# ACT01_RS232_V3_0.net
KiCad netlist of a schematic drawn in Altium Designer
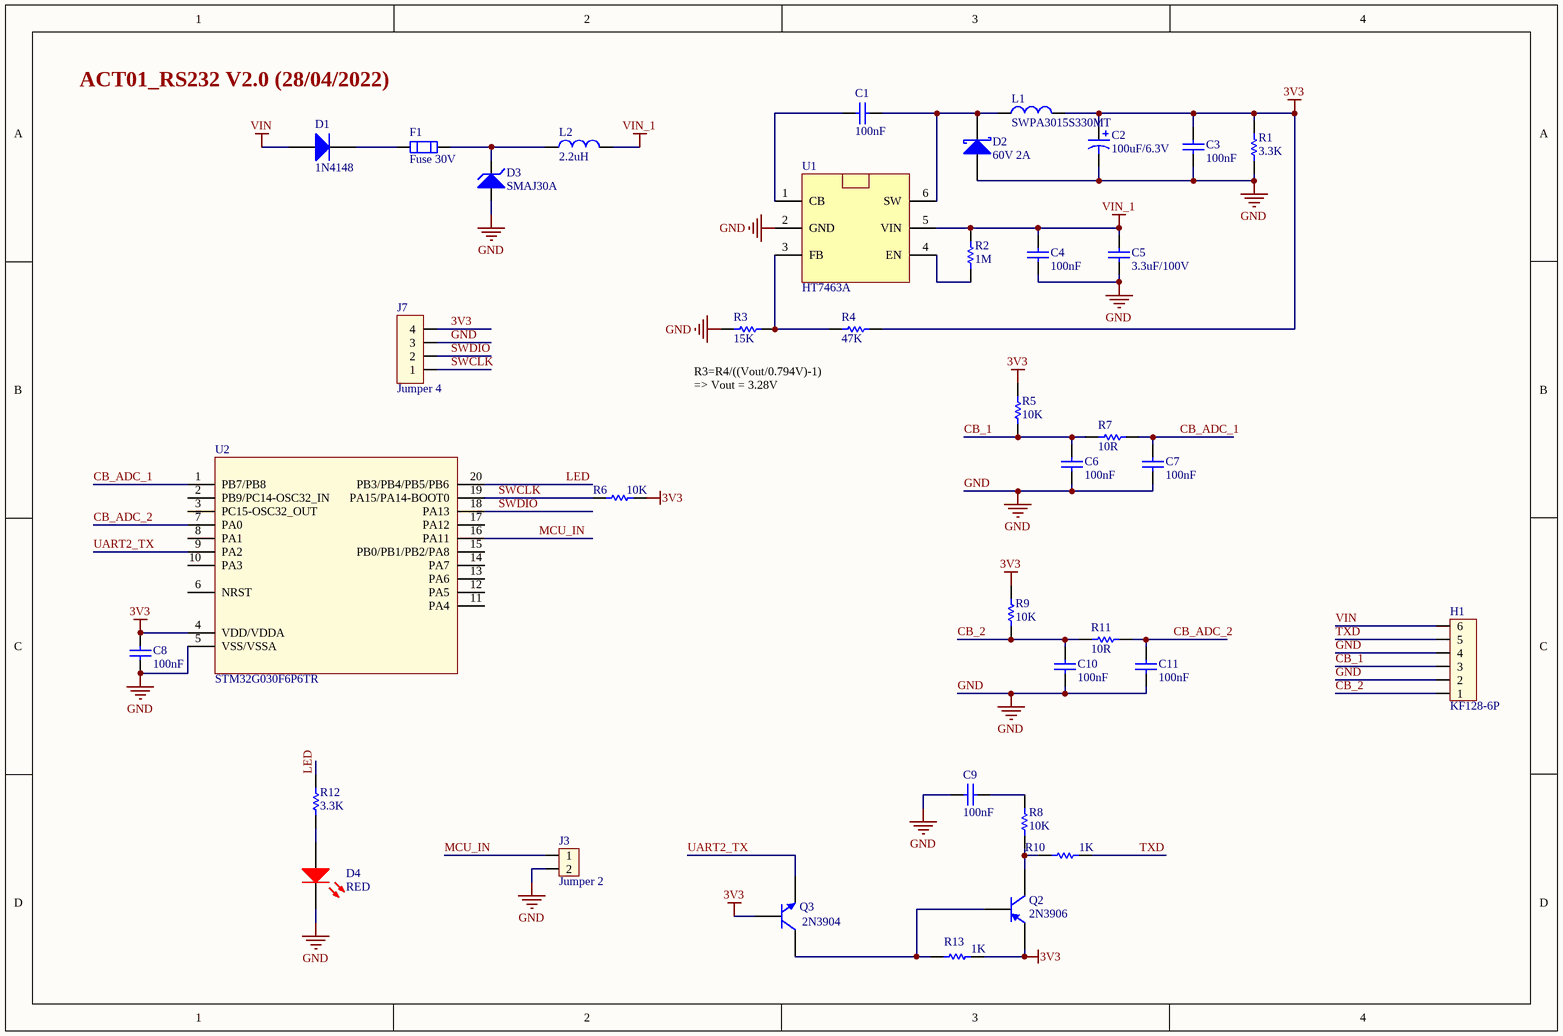
[diagram p0: ACT01_RS232 V3.0.SchDoc]

(export (version "E")
  (design (tool "Eeschema 10.0.6"))
  (components
    (comp (ref "C1")
      (value "100nF")
      (footprint "0603 - C")
      (description "CAP CER 100nF 50V C0G/NP0 0603")
      (fields (field (name "MPN") "CL10C104JB8NNNC") (field (name "MFR") "SAMSUNG"))
      (libsource (lib "Library_Chip1") (part "Cap 0603 100nF"))
    )
    (comp (ref "C2")
      (value "100uF/6.3V")
      (footprint "3528 - TANTALUM")
      (description "CAP TANT 100UF 6.3V 10% 1411")
      (fields (field (name "MPN") "T491B107K006AT") (field (name "MFR") "Kemet"))
      (libsource (lib "Library_Chip1") (part "Cap Tan 3528 100uF/6.3V"))
    )
    (comp (ref "C3")
      (value "100nF")
      (footprint "0603 - C")
      (description "CAP CER 100nF 50V C0G/NP0 0603")
      (fields (field (name "MPN") "CL10C104JB8NNNC") (field (name "MFR") "SAMSUNG"))
      (libsource (lib "Library_Chip1") (part "Cap 0603 100nF"))
    )
    (comp (ref "C4")
      (value "100nF")
      (footprint "0603 - C")
      (description "CAP CER 100nF 50V C0G/NP0 0603")
      (fields (field (name "MPN") "CL10C104JB8NNNC") (field (name "MFR") "SAMSUNG"))
      (libsource (lib "Library_Chip1") (part "Cap 0603 100nF"))
    )
    (comp (ref "C5")
      (value "3.3uF/100V")
      (footprint "1210 - C")
      (description "CAP CER 3.3UF 100V X7S 1210")
      (fields (field (name "MPN") "C3225X7S2A335M200AB") (field (name "MFR") "TDK Corporation"))
      (libsource (lib "Library_Chip1") (part "Cap 1210 3.3uF"))
    )
    (comp (ref "C6")
      (value "100nF")
      (footprint "0603 - C")
      (description "CAP CER 100nF 50V C0G/NP0 0603")
      (fields (field (name "MPN") "CL10C104JB8NNNC") (field (name "MFR") "SAMSUNG"))
      (libsource (lib "Library_Chip1") (part "Cap 0603 100nF"))
    )
    (comp (ref "C7")
      (value "100nF")
      (footprint "0603 - C")
      (description "CAP CER 100nF 50V C0G/NP0 0603")
      (fields (field (name "MPN") "CL10C104JB8NNNC") (field (name "MFR") "SAMSUNG"))
      (libsource (lib "Library_Chip1") (part "Cap 0603 100nF"))
    )
    (comp (ref "C8")
      (value "100nF")
      (footprint "0603 - C")
      (description "CAP CER 100nF 50V C0G/NP0 0603")
      (fields (field (name "MPN") "CL10C104JB8NNNC") (field (name "MFR") "SAMSUNG"))
      (libsource (lib "Library_Chip") (part "Cap 0603 100nF"))
    )
    (comp (ref "C9")
      (value "100nF")
      (footprint "0603 - C")
      (description "CAP CER 100nF 50V C0G/NP0 0603")
      (fields (field (name "MPN") "CL10C104JB8NNNC") (field (name "MFR") "SAMSUNG"))
      (libsource (lib "Library_Chip") (part "Cap 0603 100nF"))
    )
    (comp (ref "C10")
      (value "100nF")
      (footprint "0603 - C")
      (description "CAP CER 100nF 50V C0G/NP0 0603")
      (fields (field (name "MPN") "CL10C104JB8NNNC") (field (name "MFR") "SAMSUNG"))
      (libsource (lib "Library_Chip1") (part "Cap 0603 100nF"))
    )
    (comp (ref "C11")
      (value "100nF")
      (footprint "0603 - C")
      (description "CAP CER 100nF 50V C0G/NP0 0603")
      (fields (field (name "MPN") "CL10C104JB8NNNC") (field (name "MFR") "SAMSUNG"))
      (libsource (lib "Library_Chip1") (part "Cap 0603 100nF"))
    )
    (comp (ref "D1")
      (value "1N4148")
      (footprint "SOD-123")
      (description "DIODE GEN PURP 100V 300MA SOD123")
      (fields (field (name "MPN") "1N4148W-7-F") (field (name "MFR") "DIODES"))
      (libsource (lib "Library_Chip") (part "Diode 1N4148"))
    )
    (comp (ref "D2")
      (value "60V 2A")
      (footprint "SOD-123")
      (description "DIODE SCHOTTKY 60V 2A SOD123W")
      (fields (field (name "MPN") "PMEG6020ER,115") (field (name "MFR") "NXP"))
      (libsource (lib "Library_Chip") (part "Diode PMEG6020ER"))
    )
    (comp (ref "D3")
      (value "SMAJ30A")
      (footprint "Diode - SMA")
      (description "TVS DIODE 30V 48.4V DO214AC")
      (fields (field (name "MFR") "Littelfuse Inc."))
      (libsource (lib "Library_Chip") (part "Diode SMAJ30A"))
    )
    (comp (ref "D4")
      (value "RED")
      (footprint "LED - 0603 - R")
      (description "LED RED CLEAR 0603 SMD")
      (fields (field (name "MFR") "Everlight") (field (name "MPN") "QTLP601CRTR"))
      (libsource (lib "Library_Chip") (part "LED 0603 RED"))
    )
    (comp (ref "F1")
      (value "Fuse 30V")
      (footprint "1206 - Fuse")
      (description "PTC RESET FUSE 30V 0.125A 1206")
      (fields (field (name "MFR") "BrightKing") (field (name "MPN") "SMD1206B012TF"))
      (libsource (lib "Library_Chip") (part "Fuse 30V - 0.125A"))
    )
    (comp (ref "H1")
      (value "KF128-6P")
      (footprint "KF128 - 6P")
      (description "6-Pin Plug-in Terminal Block Connector 5.08mm Pitch Through Hole")
      (fields (field (name "MPN") "KF128 - 6P") (field (name "MFR") "China"))
      (libsource (lib "Library_ Connector") (part "HD KF128 6P"))
    )
    (comp (ref "J3")
      (value "Jumper 2")
      (footprint "JP2")
      (description "Jumper 2, 2.54mmx2")
      (libsource (lib "Library_ Connector") (part "JP2"))
    )
    (comp (ref "J7")
      (value "Jumper 4")
      (footprint "JP4 2mm")
      (description "Jumper 4, 2.54mmx4")
      (libsource (lib "Library_ Connector") (part "JP4"))
    )
    (comp (ref "L1")
      (value "SWPA3015S330MT")
      (footprint "IND_3x3")
      (description "FIXED IND 33UH 430MA 1.066OHM SM")
      (fields (field (name "MFR") "Shenzhen Sunlord Electronics Co., Ltd."))
      (libsource (lib "Library_Chip") (part "Inductor 33uH"))
    )
    (comp (ref "L2")
      (value "2.2uH")
      (footprint "1210 - L")
      (description "FIXED IND 2.2UH 1.6A 76 MOHM SMD")
      (fields (field (name "MPN") "LQH32PN2R2NN0") (field (name "MFR") "Murata"))
      (libsource (lib "Library_Chip") (part "Inductor 3225 2.2uH"))
    )
    (comp (ref "Q2")
      (value "2N3906")
      (footprint "SOT23B")
      (description "TRANS PNP 40V 0.2A SOT23")
      (fields (field (name "MPN") "MMBT3906") (field (name "MFR") "Fairchild"))
      (libsource (lib "Library_Chip") (part "Transistor 2N3906"))
    )
    (comp (ref "Q3")
      (value "2N3904")
      (footprint "SOT23B")
      (description "TRANS NPN 40V 0.2A SOT-23")
      (fields (field (name "MPN") "MMBT3904") (field (name "MFR") "Fairchild"))
      (libsource (lib "Library_Chip") (part "Transistor 2N3904"))
    )
    (comp (ref "R1")
      (value "3.3K")
      (footprint "0603 - R")
      (description "RES SMD 3.3K OHM 1% 1/10W 0603")
      (fields (field (name "MFR") "Yageo") (field (name "MPN") "RC0603FR-073K3L"))
      (libsource (lib "Library_Chip") (part "Res 0603 3.3K"))
    )
    (comp (ref "R2")
      (value "1M")
      (footprint "0603 - R")
      (description "RES SMD 1M OHM 1% 1/10W 0603")
      (fields (field (name "MFR") "Yageo") (field (name "MPN") "RC0603FR-071ML"))
      (libsource (lib "Library_Chip1") (part "Res 0603 1M"))
    )
    (comp (ref "R3")
      (value "15K")
      (footprint "0603 - R")
      (description "RES SMD 15K OHM 1% 1/10W 0603")
      (fields (field (name "MFR") "Yageo") (field (name "MPN") "RC0603FR-0715KL"))
      (libsource (lib "Library_Chip1") (part "Res 0603 15K"))
    )
    (comp (ref "R4")
      (value "47K")
      (footprint "0603 - R")
      (description "RES SMD 47K OHM 1% 1/10W 0603")
      (fields (field (name "MFR") "Yageo") (field (name "MPN") "RE0603FRE0747KL"))
      (libsource (lib "Library_Chip1") (part "Res 0603 47K"))
    )
    (comp (ref "R5")
      (value "10K")
      (footprint "0603 - R")
      (description "RES SMD 10K OHM 1% 1/10W 0603")
      (fields (field (name "MFR") "Yageo") (field (name "MPN") "RC0603FR-0710KL"))
      (libsource (lib "Library_Chip") (part "Res 0603 10K"))
    )
    (comp (ref "R6")
      (value "10K")
      (footprint "0603 - R")
      (description "RES SMD 10K OHM 1% 1/10W 0603")
      (fields (field (name "MFR") "Yageo") (field (name "MPN") "RC0603FR-0710KL"))
      (libsource (lib "Library_Chip") (part "Res 0603 10K"))
    )
    (comp (ref "R7")
      (value "10R")
      (footprint "0603 - R")
      (description "RES SMD 10 OHM 1% 1/10W 0603")
      (fields (field (name "MFR") "Yageo") (field (name "MPN") "RC0603FR-0710RL"))
      (libsource (lib "Library_Chip") (part "Res 0603 10R"))
    )
    (comp (ref "R8")
      (value "10K")
      (footprint "0603 - R")
      (description "RES SMD 10K OHM 1% 1/10W 0603")
      (fields (field (name "MFR") "Yageo") (field (name "MPN") "RC0603FR-0710KL"))
      (libsource (lib "Library_Chip") (part "Res 0603 10K"))
    )
    (comp (ref "R9")
      (value "10K")
      (footprint "0603 - R")
      (description "RES SMD 10K OHM 1% 1/10W 0603")
      (fields (field (name "MFR") "Yageo") (field (name "MPN") "RC0603FR-0710KL"))
      (libsource (lib "Library_Chip") (part "Res 0603 10K"))
    )
    (comp (ref "R10")
      (value "1K")
      (footprint "0603 - R")
      (description "RES SMD 1K OHM 1% 1/10W 0603")
      (fields (field (name "MFR") "Yageo") (field (name "MPN") "RC0603FR-071KL"))
      (libsource (lib "Library_Chip") (part "Res 0603 1K"))
    )
    (comp (ref "R11")
      (value "10R")
      (footprint "0603 - R")
      (description "RES SMD 10 OHM 1% 1/10W 0603")
      (fields (field (name "MFR") "Yageo") (field (name "MPN") "RC0603FR-0710RL"))
      (libsource (lib "Library_Chip") (part "Res 0603 10R"))
    )
    (comp (ref "R12")
      (value "3.3K")
      (footprint "0603 - R")
      (description "RES SMD 3.3K OHM 1% 1/10W 0603")
      (fields (field (name "MFR") "Yageo") (field (name "MPN") "RC0603FR-073K3L"))
      (libsource (lib "Library_Chip") (part "Res 0603 3.3K"))
    )
    (comp (ref "R13")
      (value "1K")
      (footprint "0603 - R")
      (description "RES SMD 1K OHM 1% 1/10W 0603")
      (fields (field (name "MFR") "Yageo") (field (name "MPN") "RC0603FR-071KL"))
      (libsource (lib "Library_Chip") (part "Res 0603 1K"))
    )
    (comp (ref "U1")
      (value "HT7463A")
      (footprint "SOT23-6_L")
      (description "52V/600mA, 1.25MHz/550kHz\r\nAsynchronous Step Down Converter")
      (fields (field (name "MFR") "Holtek"))
      (libsource (lib "Library_IC") (part "HT7463A/HT7463B"))
    )
    (comp (ref "U2")
      (value "STM32G030F6P6TR")
      (footprint "TSSOP20")
      (description "IC MCU 32BIT 32KB FLASH 20TSSOP")
      (fields (field (name "MPN") "STMicroelectronics"))
      (libsource (lib "Library_IC") (part "STM32G030F6P6TR"))
    )
  )
  (nets
    (net (code "1") (name "/CB_1") (class "Default")
      (node (ref "C6") (pin "2") (pinfunction "2_2") (pintype "passive"))
      (node (ref "H1") (pin "3") (pinfunction "3_3") (pintype "passive"))
      (node (ref "R5") (pin "1") (pinfunction "1_1") (pintype "passive"))
      (node (ref "R7") (pin "1") (pinfunction "1_1") (pintype "passive"))
    )
    (net (code "2") (name "/CB_2") (class "Default")
      (node (ref "C10") (pin "2") (pinfunction "2_2") (pintype "passive"))
      (node (ref "H1") (pin "1") (pinfunction "1_1") (pintype "passive"))
      (node (ref "R11") (pin "1") (pinfunction "1_1") (pintype "passive"))
      (node (ref "R9") (pin "1") (pinfunction "1_1") (pintype "passive"))
    )
    (net (code "3") (name "/CB_ADC_1") (class "Default")
      (node (ref "C7") (pin "2") (pinfunction "2_2") (pintype "passive"))
      (node (ref "R7") (pin "2") (pinfunction "2_2") (pintype "passive"))
      (node (ref "U2") (pin "1") (pinfunction "PB7/PB8_1") (pintype "power_in"))
    )
    (net (code "4") (name "/CB_ADC_2") (class "Default")
      (node (ref "C11") (pin "2") (pinfunction "2_2") (pintype "passive"))
      (node (ref "R11") (pin "2") (pinfunction "2_2") (pintype "passive"))
      (node (ref "U2") (pin "7") (pinfunction "PA0_7") (pintype "power_in"))
    )
    (net (code "5") (name "/LED") (class "Default")
      (node (ref "R12") (pin "2") (pinfunction "2_2") (pintype "passive"))
      (node (ref "U2") (pin "20") (pinfunction "PB3/PB4/PB5/PB6_20") (pintype "power_in"))
    )
    (net (code "6") (name "/MCU_IN") (class "Default")
      (node (ref "J3") (pin "1") (pinfunction "1_1") (pintype "passive"))
      (node (ref "U2") (pin "16") (pinfunction "PA11_16") (pintype "power_in"))
    )
    (net (code "7") (name "/SWCLK") (class "Default")
      (node (ref "J7") (pin "1") (pinfunction "1_1") (pintype "passive"))
      (node (ref "R6") (pin "1") (pinfunction "1_1") (pintype "passive"))
      (node (ref "U2") (pin "19") (pinfunction "PA15/PA14-BOOT0_19") (pintype "power_in"))
    )
    (net (code "8") (name "/SWDIO") (class "Default")
      (node (ref "J7") (pin "2") (pinfunction "2_2") (pintype "passive"))
      (node (ref "U2") (pin "18") (pinfunction "PA13_18") (pintype "power_in"))
    )
    (net (code "9") (name "/TXD") (class "Default")
      (node (ref "H1") (pin "5") (pinfunction "5_5") (pintype "passive"))
      (node (ref "R10") (pin "2") (pinfunction "2_2") (pintype "passive"))
    )
    (net (code "10") (name "/UART2_TX") (class "Default")
      (node (ref "Q3") (pin "2") (pinfunction "E_2") (pintype "passive"))
      (node (ref "U2") (pin "9") (pinfunction "PA2_9") (pintype "power_in"))
    )
    (net (code "11") (name "3V3") (class "Default")
      (node (ref "C2") (pin "1") (pinfunction "1_1") (pintype "passive"))
      (node (ref "C3") (pin "2") (pinfunction "2_2") (pintype "passive"))
      (node (ref "C8") (pin "2") (pinfunction "2_2") (pintype "passive"))
      (node (ref "J7") (pin "4") (pinfunction "4_4") (pintype "passive"))
      (node (ref "L1") (pin "2") (pinfunction "2_2") (pintype "passive"))
      (node (ref "Q2") (pin "2") (pinfunction "E_2") (pintype "passive"))
      (node (ref "Q3") (pin "1") (pinfunction "B_1") (pintype "passive"))
      (node (ref "R1") (pin "2") (pinfunction "2_2") (pintype "passive"))
      (node (ref "R13") (pin "2") (pinfunction "2_2") (pintype "passive"))
      (node (ref "R4") (pin "2") (pinfunction "2_2") (pintype "passive"))
      (node (ref "R5") (pin "2") (pinfunction "2_2") (pintype "passive"))
      (node (ref "R6") (pin "2") (pinfunction "2_2") (pintype "passive"))
      (node (ref "R9") (pin "2") (pinfunction "2_2") (pintype "passive"))
      (node (ref "U2") (pin "4") (pinfunction "VDD/VDDA_4") (pintype "power_in"))
    )
    (net (code "12") (name "GND") (class "Default")
      (node (ref "C10") (pin "1") (pinfunction "1_1") (pintype "passive"))
      (node (ref "C11") (pin "1") (pinfunction "1_1") (pintype "passive"))
      (node (ref "C2") (pin "2") (pinfunction "2_2") (pintype "passive"))
      (node (ref "C3") (pin "1") (pinfunction "1_1") (pintype "passive"))
      (node (ref "C4") (pin "1") (pinfunction "1_1") (pintype "passive"))
      (node (ref "C5") (pin "1") (pinfunction "1_1") (pintype "passive"))
      (node (ref "C6") (pin "1") (pinfunction "1_1") (pintype "passive"))
      (node (ref "C7") (pin "1") (pinfunction "1_1") (pintype "passive"))
      (node (ref "C8") (pin "1") (pinfunction "1_1") (pintype "passive"))
      (node (ref "C9") (pin "1") (pinfunction "1_1") (pintype "passive"))
      (node (ref "D2") (pin "1") (pinfunction "A_1") (pintype "passive"))
      (node (ref "D3") (pin "1") (pinfunction "A_1") (pintype "passive"))
      (node (ref "D4") (pin "2") (pinfunction "K_2") (pintype "passive"))
      (node (ref "H1") (pin "2") (pinfunction "2_2") (pintype "passive"))
      (node (ref "H1") (pin "4") (pinfunction "4_4") (pintype "passive"))
      (node (ref "J3") (pin "2") (pinfunction "2_2") (pintype "passive"))
      (node (ref "J7") (pin "3") (pinfunction "3_3") (pintype "passive"))
      (node (ref "R1") (pin "1") (pinfunction "1_1") (pintype "passive"))
      (node (ref "R3") (pin "2") (pinfunction "2_2") (pintype "passive"))
      (node (ref "U1") (pin "2") (pinfunction "GND_2") (pintype "power_in"))
      (node (ref "U2") (pin "5") (pinfunction "VSS/VSSA_5") (pintype "power_in"))
    )
    (net (code "13") (name "Net-(C9-Pad2)") (class "Default")
      (node (ref "C9") (pin "2") (pinfunction "2_2") (pintype "passive"))
      (node (ref "R8") (pin "1") (pinfunction "1_1") (pintype "passive"))
    )
    (net (code "14") (name "Net-(D1-K)") (class "Default")
      (node (ref "D1") (pin "2") (pinfunction "K_2") (pintype "passive"))
      (node (ref "F1") (pin "1") (pinfunction "1_1") (pintype "passive"))
    )
    (net (code "15") (name "Net-(D2-K)") (class "Default")
      (node (ref "C1") (pin "2") (pinfunction "2_2") (pintype "passive"))
      (node (ref "D2") (pin "2") (pinfunction "K_2") (pintype "passive"))
      (node (ref "L1") (pin "1") (pinfunction "1_1") (pintype "passive"))
      (node (ref "U1") (pin "6") (pinfunction "SW_6") (pintype "power_in"))
    )
    (net (code "16") (name "Net-(D3-K)") (class "Default")
      (node (ref "D3") (pin "2") (pinfunction "K_2") (pintype "passive"))
      (node (ref "F1") (pin "2") (pinfunction "2_2") (pintype "passive"))
      (node (ref "L2") (pin "1") (pinfunction "1_1") (pintype "passive"))
    )
    (net (code "17") (name "Net-(D4-A)") (class "Default")
      (node (ref "D4") (pin "1") (pinfunction "A_1") (pintype "passive"))
      (node (ref "R12") (pin "1") (pinfunction "1_1") (pintype "passive"))
    )
    (net (code "18") (name "Net-(Q2-B)") (class "Default")
      (node (ref "Q2") (pin "1") (pinfunction "B_1") (pintype "passive"))
      (node (ref "Q3") (pin "3") (pinfunction "C_3") (pintype "passive"))
      (node (ref "R13") (pin "1") (pinfunction "1_1") (pintype "passive"))
    )
    (net (code "19") (name "Net-(Q2-C)") (class "Default")
      (node (ref "Q2") (pin "3") (pinfunction "C_3") (pintype "passive"))
      (node (ref "R10") (pin "1") (pinfunction "1_1") (pintype "passive"))
      (node (ref "R8") (pin "2") (pinfunction "2_2") (pintype "passive"))
    )
    (net (code "20") (name "Net-(U1-CB)") (class "Default")
      (node (ref "C1") (pin "1") (pinfunction "1_1") (pintype "passive"))
      (node (ref "U1") (pin "1") (pinfunction "CB_1") (pintype "power_in"))
    )
    (net (code "21") (name "Net-(U1-EN)") (class "Default")
      (node (ref "R2") (pin "1") (pinfunction "1_1") (pintype "passive"))
      (node (ref "U1") (pin "4") (pinfunction "EN_4") (pintype "power_in"))
    )
    (net (code "22") (name "Net-(U1-FB)") (class "Default")
      (node (ref "R3") (pin "1") (pinfunction "1_1") (pintype "passive"))
      (node (ref "R4") (pin "1") (pinfunction "1_1") (pintype "passive"))
      (node (ref "U1") (pin "3") (pinfunction "FB_3") (pintype "power_in"))
    )
    (net (code "23") (name "VIN") (class "Default")
      (node (ref "D1") (pin "1") (pinfunction "A_1") (pintype "passive"))
      (node (ref "H1") (pin "6") (pinfunction "6_6") (pintype "passive"))
    )
    (net (code "24") (name "VIN_1") (class "Default")
      (node (ref "C4") (pin "2") (pinfunction "2_2") (pintype "passive"))
      (node (ref "C5") (pin "2") (pinfunction "2_2") (pintype "passive"))
      (node (ref "L2") (pin "2") (pinfunction "2_2") (pintype "passive"))
      (node (ref "R2") (pin "2") (pinfunction "2_2") (pintype "passive"))
      (node (ref "U1") (pin "5") (pinfunction "VIN_5") (pintype "power_in"))
    )
    (net (code "25") (name "unconnected-(U2-NRST-Pad6)") (class "Default")
      (node (ref "U2") (pin "6") (pinfunction "NRST_6") (pintype "power_in"))
    )
    (net (code "26") (name "unconnected-(U2-PA1-Pad8)") (class "Default")
      (node (ref "U2") (pin "8") (pinfunction "PA1_8") (pintype "power_in"))
    )
    (net (code "27") (name "unconnected-(U2-PA3-Pad10)") (class "Default")
      (node (ref "U2") (pin "10") (pinfunction "PA3_10") (pintype "power_in"))
    )
    (net (code "28") (name "unconnected-(U2-PA4-Pad11)") (class "Default")
      (node (ref "U2") (pin "11") (pinfunction "PA4_11") (pintype "power_in"))
    )
    (net (code "29") (name "unconnected-(U2-PA5-Pad12)") (class "Default")
      (node (ref "U2") (pin "12") (pinfunction "PA5_12") (pintype "power_in"))
    )
    (net (code "30") (name "unconnected-(U2-PA6-Pad13)") (class "Default")
      (node (ref "U2") (pin "13") (pinfunction "PA6_13") (pintype "power_in"))
    )
    (net (code "31") (name "unconnected-(U2-PA7-Pad14)") (class "Default")
      (node (ref "U2") (pin "14") (pinfunction "PA7_14") (pintype "power_in"))
    )
    (net (code "32") (name "unconnected-(U2-PA12-Pad17)") (class "Default")
      (node (ref "U2") (pin "17") (pinfunction "PA12_17") (pintype "power_in"))
    )
    (net (code "33") (name "unconnected-(U2-PB0{slash}PB1{slash}PB2{slash}PA8-Pad15)") (class "Default")
      (node (ref "U2") (pin "15") (pinfunction "PB0/PB1/PB2/PA8_15") (pintype "power_in"))
    )
    (net (code "34") (name "unconnected-(U2-PB9{slash}PC14-OSC32_IN-Pad2)") (class "Default")
      (node (ref "U2") (pin "2") (pinfunction "PB9/PC14-OSC32_IN_2") (pintype "power_in"))
    )
    (net (code "35") (name "unconnected-(U2-PC15-OSC32_OUT-Pad3)") (class "Default")
      (node (ref "U2") (pin "3") (pinfunction "PC15-OSC32_OUT_3") (pintype "power_in"))
    )
  )
)
